# SCH_wiring_diagram_phws_2026-05-13.net
KiCad netlist of a schematic drawn in EasyEDA
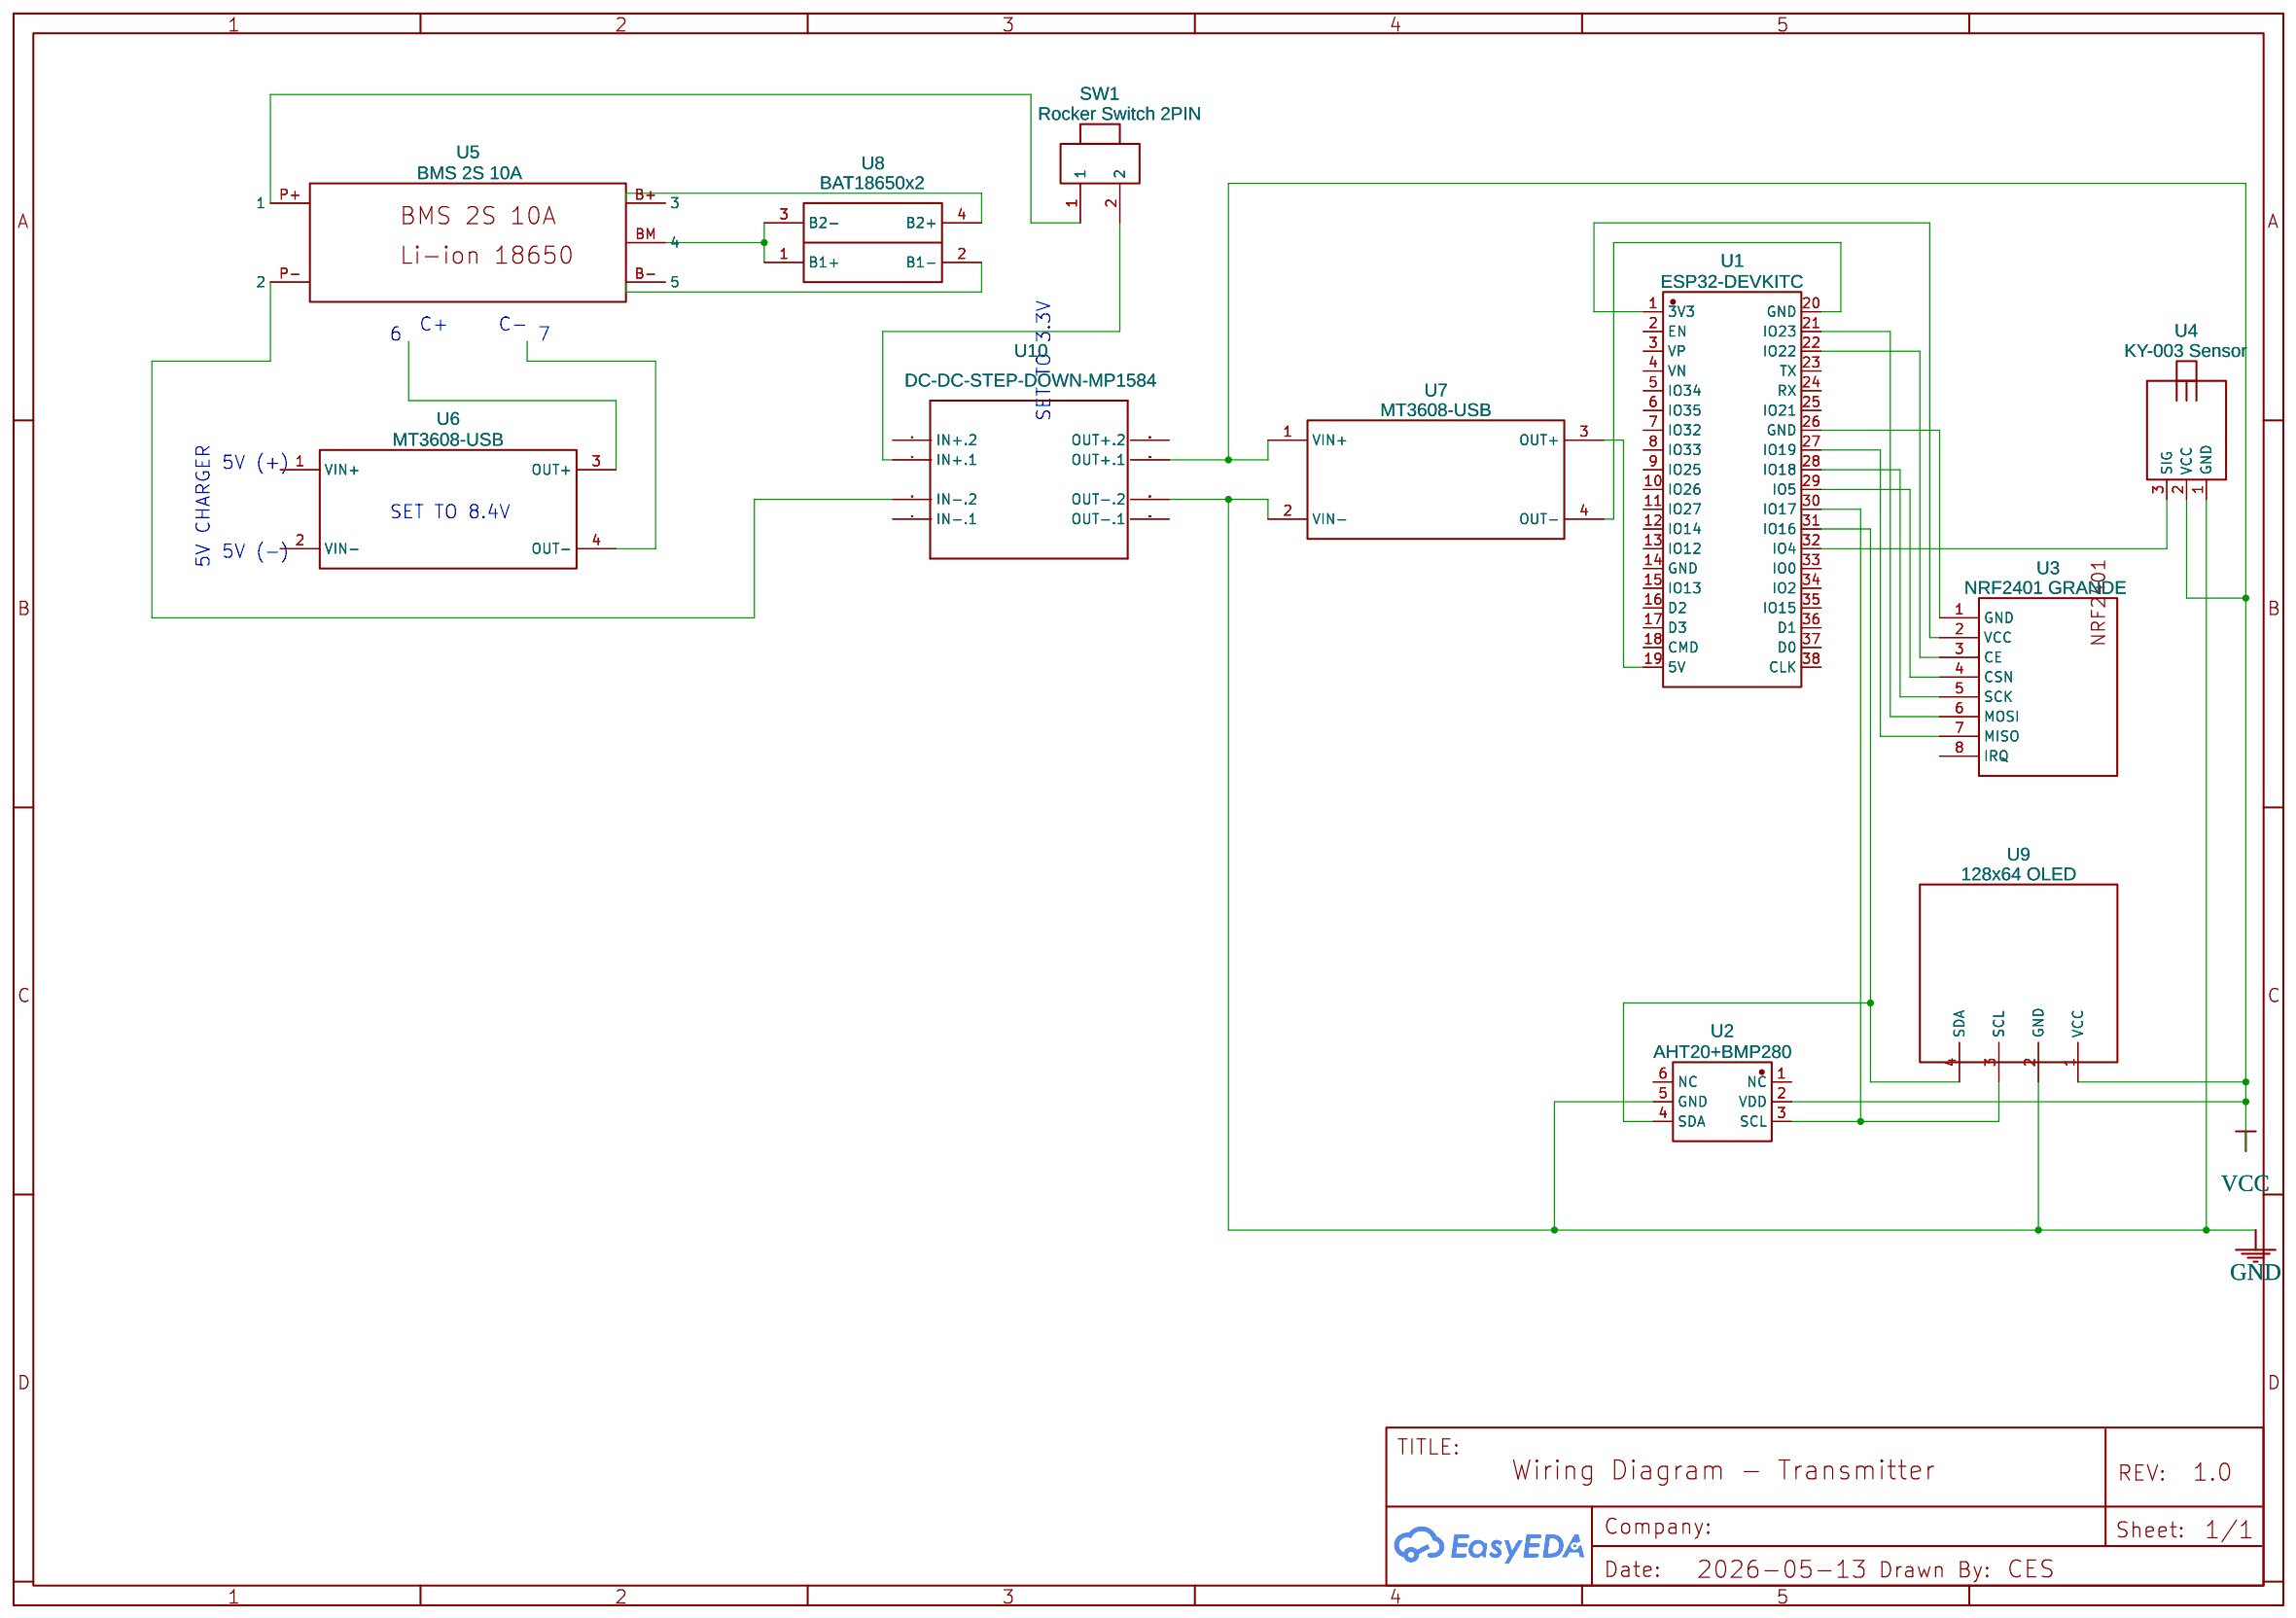
[diagram p0: schematic sheet]

(export (version "E")
  (design (tool "Eeschema 10.0.6"))
  (components
    (comp (ref "SW1")
      (value "Rocker Switch 2PIN")
      (fields
        (field (name "Manufacturer Part") "Rocker switch601-10211BB")
        (field (name "Manufacturer") "BBJ")
      )
      (libsource (lib "") (part "Rocker Switch 2PIN"))
    )
    (comp (ref "U1")
      (value "ESP32-DEVKITC")
      (fields
        (field (name "Manufacturer Part") "ESP32-DevKitC")
        (field (name "Manufacturer") "ESPRESSIF(乐鑫)")
      )
      (libsource (lib "") (part "ESP32-DEVKITC"))
    )
    (comp (ref "U2")
      (value "AHT20+BMP280")
      (fields (field (name "Manufacturer Part") "AHT20-F") (field (name "Manufacturer") "广州奥松"))
      (libsource (lib "") (part "AHT20-F"))
    )
    (comp (ref "U3") (value "NRF2401 GRANDE") (libsource (lib "") (part "NRF2401_GRANDE")))
    (comp (ref "U4") (value "KY-003 Sensor") (libsource (lib "") (part "KY-003 Hall Effect Sensor")))
    (comp (ref "U5") (value "BMS 2S 10A") (libsource (lib "") (part "BMS 2S 10a C")))
    (comp (ref "U6") (value "MT3608-USB") (libsource (lib "") (part "MT3608-USB")))
    (comp (ref "U7") (value "MT3608-USB") (libsource (lib "") (part "MT3608-USB")))
    (comp (ref "U8") (value "BAT18650x2") (libsource (lib "") (part "BAT18650x2")))
    (comp (ref "U9") (value "128x64 OLED") (libsource (lib "") (part "128x64 Oled VCCat1 GNDat2")))
    (comp (ref "U10") (value "DC-DC-STEP-DOWN-MP1584") (libsource (lib "") (part "DC-DC-STEP-DOWN-MP1584")))
  )
  (nets
    (net (code "1") (name "GND") (class "Default")
      (node (ref "U10") (pin "OUT-.2") (pinfunction "OUT-.2_OUT-.2") (pintype "bidirectional"))
      (node (ref "U2") (pin "5") (pinfunction "GND_5") (pintype "unspecified"))
      (node (ref "U4") (pin "1") (pinfunction "GND_1") (pintype "unspecified"))
      (node (ref "U7") (pin "2") (pinfunction "VIN-_2") (pintype "unspecified"))
      (node (ref "U9") (pin "2") (pinfunction "GND_2") (pintype "unspecified"))
    )
    (net (code "2") (name "Net-(SW1-Pad2)") (class "Default")
      (node (ref "SW1") (pin "2") (pinfunction "2_2") (pintype "unspecified"))
      (node (ref "U10") (pin "IN+.1") (pinfunction "IN+.1_IN+.1") (pintype "bidirectional"))
    )
    (net (code "3") (name "Net-(U1-3V3)") (class "Default")
      (node (ref "U1") (pin "1") (pinfunction "3V3_1") (pintype "unspecified"))
      (node (ref "U3") (pin "2") (pinfunction "VCC_2") (pintype "unspecified"))
    )
    (net (code "4") (name "Net-(U1-5V)") (class "Default")
      (node (ref "U1") (pin "19") (pinfunction "5V_19") (pintype "unspecified"))
      (node (ref "U7") (pin "3") (pinfunction "OUT+_3") (pintype "unspecified"))
    )
    (net (code "5") (name "Net-(U1-IO4)") (class "Default")
      (node (ref "U1") (pin "32") (pinfunction "IO4_32") (pintype "unspecified"))
      (node (ref "U4") (pin "3") (pinfunction "SIG_3") (pintype "unspecified"))
    )
    (net (code "6") (name "Net-(U1-IO5)") (class "Default")
      (node (ref "U1") (pin "29") (pinfunction "IO5_29") (pintype "unspecified"))
      (node (ref "U3") (pin "4") (pinfunction "CSN_4") (pintype "unspecified"))
    )
    (net (code "7") (name "Net-(U1-IO16)") (class "Default")
      (node (ref "U1") (pin "31") (pinfunction "IO16_31") (pintype "unspecified"))
      (node (ref "U2") (pin "4") (pinfunction "SDA_4") (pintype "unspecified"))
      (node (ref "U9") (pin "4") (pinfunction "SDA_4") (pintype "unspecified"))
    )
    (net (code "8") (name "Net-(U1-IO17)") (class "Default")
      (node (ref "U1") (pin "30") (pinfunction "IO17_30") (pintype "unspecified"))
      (node (ref "U2") (pin "3") (pinfunction "SCL_3") (pintype "unspecified"))
      (node (ref "U9") (pin "3") (pinfunction "SCL_3") (pintype "unspecified"))
    )
    (net (code "9") (name "Net-(U1-IO18)") (class "Default")
      (node (ref "U1") (pin "28") (pinfunction "IO18_28") (pintype "unspecified"))
      (node (ref "U3") (pin "5") (pinfunction "SCK_5") (pintype "unspecified"))
    )
    (net (code "10") (name "Net-(U1-IO19)") (class "Default")
      (node (ref "U1") (pin "27") (pinfunction "IO19_27") (pintype "unspecified"))
      (node (ref "U3") (pin "7") (pinfunction "MISO_7") (pintype "unspecified"))
    )
    (net (code "11") (name "Net-(U1-IO22)") (class "Default")
      (node (ref "U1") (pin "22") (pinfunction "IO22_22") (pintype "unspecified"))
      (node (ref "U3") (pin "3") (pinfunction "CE_3") (pintype "unspecified"))
    )
    (net (code "12") (name "Net-(U1-IO23)") (class "Default")
      (node (ref "U1") (pin "21") (pinfunction "IO23_21") (pintype "unspecified"))
      (node (ref "U3") (pin "6") (pinfunction "MOSI_6") (pintype "unspecified"))
    )
    (net (code "13") (name "Net-(U3-GND)") (class "Default")
      (node (ref "U1") (pin "26") (pinfunction "GND_26") (pintype "unspecified"))
      (node (ref "U3") (pin "1") (pinfunction "GND_1") (pintype "unspecified"))
    )
    (net (code "14") (name "Net-(U5-1)") (class "Default")
      (node (ref "SW1") (pin "1") (pinfunction "1_1") (pintype "unspecified"))
      (node (ref "U5") (pin "P+") (pinfunction "1_P+") (pintype "unspecified"))
    )
    (net (code "15") (name "Net-(U5-2)") (class "Default")
      (node (ref "U10") (pin "IN-.2") (pinfunction "IN-.2_IN-.2") (pintype "bidirectional"))
      (node (ref "U5") (pin "P-") (pinfunction "2_P-") (pintype "unspecified"))
    )
    (net (code "16") (name "Net-(U5-3)") (class "Default")
      (node (ref "U5") (pin "B+") (pinfunction "3_B+") (pintype "unspecified"))
      (node (ref "U8") (pin "4") (pinfunction "B2+_4") (pintype "unspecified"))
    )
    (net (code "17") (name "Net-(U5-4)") (class "Default")
      (node (ref "U5") (pin "BM") (pinfunction "4_BM") (pintype "unspecified"))
      (node (ref "U8") (pin "1") (pinfunction "B1+_1") (pintype "unspecified"))
      (node (ref "U8") (pin "3") (pinfunction "B2-_3") (pintype "unspecified"))
    )
    (net (code "18") (name "Net-(U5-5)") (class "Default")
      (node (ref "U5") (pin "B-") (pinfunction "5_B-") (pintype "unspecified"))
      (node (ref "U8") (pin "2") (pinfunction "B1-_2") (pintype "unspecified"))
    )
    (net (code "19") (name "Net-(U7-OUT-)") (class "Default")
      (node (ref "U1") (pin "20") (pinfunction "GND_20") (pintype "unspecified"))
      (node (ref "U7") (pin "4") (pinfunction "OUT-_4") (pintype "unspecified"))
    )
    (net (code "20") (name "VCC") (class "Default")
      (node (ref "U10") (pin "OUT+.1") (pinfunction "OUT+.1_OUT+.1") (pintype "bidirectional"))
      (node (ref "U2") (pin "2") (pinfunction "VDD_2") (pintype "unspecified"))
      (node (ref "U4") (pin "2") (pinfunction "VCC_2") (pintype "unspecified"))
      (node (ref "U7") (pin "1") (pinfunction "VIN+_1") (pintype "unspecified"))
      (node (ref "U9") (pin "1") (pinfunction "VCC_1") (pintype "unspecified"))
    )
    (net (code "21") (name "unconnected-(U1-CLK-Pad38)") (class "Default")
      (node (ref "U1") (pin "38") (pinfunction "CLK_38") (pintype "unspecified"))
    )
    (net (code "22") (name "unconnected-(U1-CMD-Pad18)") (class "Default")
      (node (ref "U1") (pin "18") (pinfunction "CMD_18") (pintype "unspecified"))
    )
    (net (code "23") (name "unconnected-(U1-D0-Pad37)") (class "Default")
      (node (ref "U1") (pin "37") (pinfunction "D0_37") (pintype "unspecified"))
    )
    (net (code "24") (name "unconnected-(U1-D1-Pad36)") (class "Default")
      (node (ref "U1") (pin "36") (pinfunction "D1_36") (pintype "unspecified"))
    )
    (net (code "25") (name "unconnected-(U1-D2-Pad16)") (class "Default")
      (node (ref "U1") (pin "16") (pinfunction "D2_16") (pintype "unspecified"))
    )
    (net (code "26") (name "unconnected-(U1-D3-Pad17)") (class "Default")
      (node (ref "U1") (pin "17") (pinfunction "D3_17") (pintype "unspecified"))
    )
    (net (code "27") (name "unconnected-(U1-EN-Pad2)") (class "Default")
      (node (ref "U1") (pin "2") (pinfunction "EN_2") (pintype "unspecified"))
    )
    (net (code "28") (name "unconnected-(U1-GND-Pad14)") (class "Default")
      (node (ref "U1") (pin "14") (pinfunction "GND_14") (pintype "unspecified"))
    )
    (net (code "29") (name "unconnected-(U1-IO0-Pad33)") (class "Default")
      (node (ref "U1") (pin "33") (pinfunction "IO0_33") (pintype "unspecified"))
    )
    (net (code "30") (name "unconnected-(U1-IO2-Pad34)") (class "Default")
      (node (ref "U1") (pin "34") (pinfunction "IO2_34") (pintype "unspecified"))
    )
    (net (code "31") (name "unconnected-(U1-IO12-Pad13)") (class "Default")
      (node (ref "U1") (pin "13") (pinfunction "IO12_13") (pintype "unspecified"))
    )
    (net (code "32") (name "unconnected-(U1-IO13-Pad15)") (class "Default")
      (node (ref "U1") (pin "15") (pinfunction "IO13_15") (pintype "unspecified"))
    )
    (net (code "33") (name "unconnected-(U1-IO14-Pad12)") (class "Default")
      (node (ref "U1") (pin "12") (pinfunction "IO14_12") (pintype "unspecified"))
    )
    (net (code "34") (name "unconnected-(U1-IO15-Pad35)") (class "Default")
      (node (ref "U1") (pin "35") (pinfunction "IO15_35") (pintype "unspecified"))
    )
    (net (code "35") (name "unconnected-(U1-IO21-Pad25)") (class "Default")
      (node (ref "U1") (pin "25") (pinfunction "IO21_25") (pintype "unspecified"))
    )
    (net (code "36") (name "unconnected-(U1-IO25-Pad9)") (class "Default")
      (node (ref "U1") (pin "9") (pinfunction "IO25_9") (pintype "unspecified"))
    )
    (net (code "37") (name "unconnected-(U1-IO26-Pad10)") (class "Default")
      (node (ref "U1") (pin "10") (pinfunction "IO26_10") (pintype "unspecified"))
    )
    (net (code "38") (name "unconnected-(U1-IO27-Pad11)") (class "Default")
      (node (ref "U1") (pin "11") (pinfunction "IO27_11") (pintype "unspecified"))
    )
    (net (code "39") (name "unconnected-(U1-IO32-Pad7)") (class "Default")
      (node (ref "U1") (pin "7") (pinfunction "IO32_7") (pintype "unspecified"))
    )
    (net (code "40") (name "unconnected-(U1-IO33-Pad8)") (class "Default")
      (node (ref "U1") (pin "8") (pinfunction "IO33_8") (pintype "unspecified"))
    )
    (net (code "41") (name "unconnected-(U1-IO34-Pad5)") (class "Default")
      (node (ref "U1") (pin "5") (pinfunction "IO34_5") (pintype "unspecified"))
    )
    (net (code "42") (name "unconnected-(U1-IO35-Pad6)") (class "Default")
      (node (ref "U1") (pin "6") (pinfunction "IO35_6") (pintype "unspecified"))
    )
    (net (code "43") (name "unconnected-(U1-RX-Pad24)") (class "Default")
      (node (ref "U1") (pin "24") (pinfunction "RX_24") (pintype "unspecified"))
    )
    (net (code "44") (name "unconnected-(U1-TX-Pad23)") (class "Default")
      (node (ref "U1") (pin "23") (pinfunction "TX_23") (pintype "unspecified"))
    )
    (net (code "45") (name "unconnected-(U1-VN-Pad4)") (class "Default")
      (node (ref "U1") (pin "4") (pinfunction "VN_4") (pintype "unspecified"))
    )
    (net (code "46") (name "unconnected-(U1-VP-Pad3)") (class "Default")
      (node (ref "U1") (pin "3") (pinfunction "VP_3") (pintype "unspecified"))
    )
    (net (code "47") (name "unconnected-(U2-NC-Pad1)") (class "Default")
      (node (ref "U2") (pin "1") (pinfunction "NC_1") (pintype "unspecified"))
    )
    (net (code "48") (name "unconnected-(U2-NC-Pad6)") (class "Default")
      (node (ref "U2") (pin "6") (pinfunction "NC_6") (pintype "unspecified"))
    )
    (net (code "49") (name "unconnected-(U3-IRQ-Pad8)") (class "Default")
      (node (ref "U3") (pin "8") (pinfunction "IRQ_8") (pintype "unspecified"))
    )
    (net (code "50") (name "unconnected-(U6-OUT+-Pad3)") (class "Default")
      (node (ref "U6") (pin "3") (pinfunction "OUT+_3") (pintype "unspecified"))
    )
    (net (code "51") (name "unconnected-(U6-OUT--Pad4)") (class "Default")
      (node (ref "U6") (pin "4") (pinfunction "OUT-_4") (pintype "unspecified"))
    )
    (net (code "52") (name "unconnected-(U6-VIN+-Pad1)") (class "Default")
      (node (ref "U6") (pin "1") (pinfunction "VIN+_1") (pintype "unspecified"))
    )
    (net (code "53") (name "unconnected-(U6-VIN--Pad2)") (class "Default")
      (node (ref "U6") (pin "2") (pinfunction "VIN-_2") (pintype "unspecified"))
    )
    (net (code "54") (name "unconnected-(U10-PadIN+.2)") (class "Default")
      (node (ref "U10") (pin "IN+.2") (pinfunction "IN+.2_IN+.2") (pintype "bidirectional"))
    )
    (net (code "55") (name "unconnected-(U10-PadIN-.1)") (class "Default")
      (node (ref "U10") (pin "IN-.1") (pinfunction "IN-.1_IN-.1") (pintype "bidirectional"))
    )
    (net (code "56") (name "unconnected-(U10-PadOUT+.2)") (class "Default")
      (node (ref "U10") (pin "OUT+.2") (pinfunction "OUT+.2_OUT+.2") (pintype "bidirectional"))
    )
    (net (code "57") (name "unconnected-(U10-PadOUT-.1)") (class "Default")
      (node (ref "U10") (pin "OUT-.1") (pinfunction "OUT-.1_OUT-.1") (pintype "bidirectional"))
    )
  )
)
